# Battery_Protection.net
KiCad netlist of a schematic drawn in Altium Designer
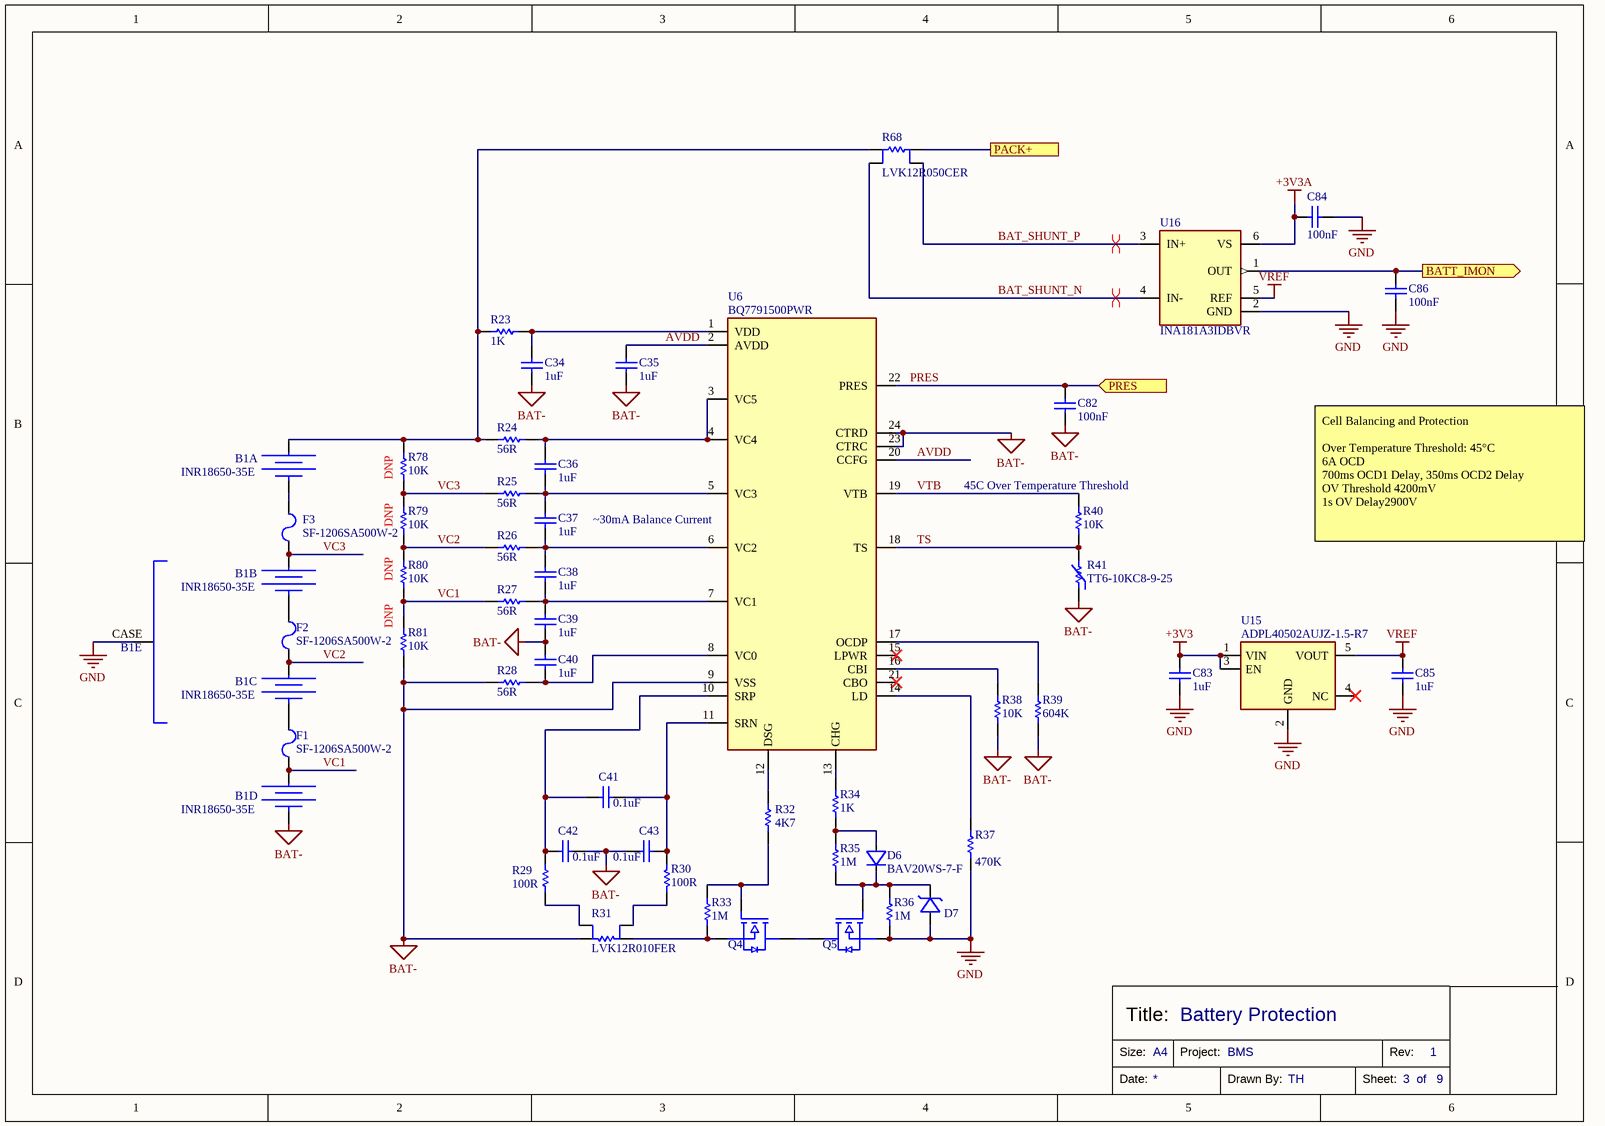
[diagram p0: Battery_Protection.SchDoc]

(export (version "E")
  (design (tool "Eeschema 10.0.6"))
  (components
    (comp (ref "B1")
      (value "INR18650-35E")
      (footprint "4S Battery Direct Solder")
      (description "Custom 4S battery component for Cubesat EPS")
      (libsource (lib "Ahristi_Library") (part "4S Battery Split"))
    )
    (comp (ref "C34")
      (value "CL10A105KB8NNNC")
      (footprint "CAPC0603X040")
      (description "1uF 50V X5R ±10% 0603 Multilayer Ceramic Capacitors MLCC - SMD/SMT ROHS")
      (fields
        (field (name "TOLERANCE") "10%")
        (field (name "DISTRIBUTOR PART NUMBER") "C15849")
        (field (name "CAPACITANCE") "1uF")
      )
      (libsource (lib "Ahristi_Library") (part "CL10A105KB8NNNC"))
    )
    (comp (ref "C35")
      (value "CL10A105KB8NNNC")
      (footprint "CAPC0603X040")
      (description "1uF 50V X5R ±10% 0603 Multilayer Ceramic Capacitors MLCC - SMD/SMT ROHS")
      (fields
        (field (name "TOLERANCE") "10%")
        (field (name "DISTRIBUTOR PART NUMBER") "C15849")
        (field (name "CAPACITANCE") "1uF")
      )
      (libsource (lib "Ahristi_Library") (part "CL10A105KB8NNNC"))
    )
    (comp (ref "C36")
      (value "CL10A105KB8NNNC")
      (footprint "CAPC0603X040")
      (description "1uF 50V X5R ±10% 0603 Multilayer Ceramic Capacitors MLCC - SMD/SMT ROHS")
      (fields
        (field (name "TOLERANCE") "10%")
        (field (name "DISTRIBUTOR PART NUMBER") "C15849")
        (field (name "CAPACITANCE") "1uF")
      )
      (libsource (lib "Ahristi_Library") (part "CL10A105KB8NNNC"))
    )
    (comp (ref "C37")
      (value "CL10A105KB8NNNC")
      (footprint "CAPC0603X040")
      (description "1uF 50V X5R ±10% 0603 Multilayer Ceramic Capacitors MLCC - SMD/SMT ROHS")
      (fields
        (field (name "TOLERANCE") "10%")
        (field (name "DISTRIBUTOR PART NUMBER") "C15849")
        (field (name "CAPACITANCE") "1uF")
      )
      (libsource (lib "Ahristi_Library") (part "CL10A105KB8NNNC"))
    )
    (comp (ref "C38")
      (value "CL10A105KB8NNNC")
      (footprint "CAPC0603X040")
      (description "1uF 50V X5R ±10% 0603 Multilayer Ceramic Capacitors MLCC - SMD/SMT ROHS")
      (fields
        (field (name "TOLERANCE") "10%")
        (field (name "DISTRIBUTOR PART NUMBER") "C15849")
        (field (name "CAPACITANCE") "1uF")
      )
      (libsource (lib "Ahristi_Library") (part "CL10A105KB8NNNC"))
    )
    (comp (ref "C39")
      (value "CL10A105KB8NNNC")
      (footprint "CAPC0603X040")
      (description "1uF 50V X5R ±10% 0603 Multilayer Ceramic Capacitors MLCC - SMD/SMT ROHS")
      (fields
        (field (name "TOLERANCE") "10%")
        (field (name "DISTRIBUTOR PART NUMBER") "C15849")
        (field (name "CAPACITANCE") "1uF")
      )
      (libsource (lib "Ahristi_Library") (part "CL10A105KB8NNNC"))
    )
    (comp (ref "C40")
      (value "CL10A105KB8NNNC")
      (footprint "CAPC0603X040")
      (description "1uF 50V X5R ±10% 0603 Multilayer Ceramic Capacitors MLCC - SMD/SMT ROHS")
      (fields
        (field (name "TOLERANCE") "10%")
        (field (name "DISTRIBUTOR PART NUMBER") "C15849")
        (field (name "CAPACITANCE") "1uF")
      )
      (libsource (lib "Ahristi_Library") (part "CL10A105KB8NNNC"))
    )
    (comp (ref "C41")
      (value "CL05B104KB5NNNC")
      (footprint "CAPC0402X020")
      (description "0.1 µF ±10% 50V Ceramic Capacitor X7R 0402 (1005 Metric)")
      (fields
        (field (name "TOLERANCE") "10%")
        (field (name "DISTRIBUTOR PART NUMBER") "1276-CL05B104KB5NNNCCT-ND")
        (field (name "CAPACITANCE") "0.1uF")
      )
      (libsource (lib "Ahristi_Library") (part "CL05B104KB5NNNC"))
    )
    (comp (ref "C42")
      (value "CL05B104KB5NNNC")
      (footprint "CAPC0402X020")
      (description "0.1 µF ±10% 50V Ceramic Capacitor X7R 0402 (1005 Metric)")
      (fields
        (field (name "TOLERANCE") "10%")
        (field (name "DISTRIBUTOR PART NUMBER") "1276-CL05B104KB5NNNCCT-ND")
        (field (name "CAPACITANCE") "0.1uF")
      )
      (libsource (lib "Ahristi_Library") (part "CL05B104KB5NNNC"))
    )
    (comp (ref "C43")
      (value "CL05B104KB5NNNC")
      (footprint "CAPC0402X020")
      (description "0.1 µF ±10% 50V Ceramic Capacitor X7R 0402 (1005 Metric)")
      (fields
        (field (name "TOLERANCE") "10%")
        (field (name "DISTRIBUTOR PART NUMBER") "1276-CL05B104KB5NNNCCT-ND")
        (field (name "CAPACITANCE") "0.1uF")
      )
      (libsource (lib "Ahristi_Library") (part "CL05B104KB5NNNC"))
    )
    (comp (ref "C82")
      (value "C0603C104K5RACTU")
      (footprint "CAPC0603X040")
      (description "0.1 µF ±10% 50V Ceramic Capacitor X7R 0603 (1608 Metric)")
      (fields
        (field (name "TOLERANCE") "10%")
        (field (name "DISTRIBUTOR PART NUMBER") "399-C0603C104K5RACTUCT-ND")
        (field (name "CAPACITANCE") "100nF")
      )
      (libsource (lib "Ahristi_Library") (part "C0603C104K5RACTU"))
    )
    (comp (ref "C83")
      (value "CL10A105KB8NNNC")
      (footprint "CAPC0603X040")
      (description "1uF 50V X5R ±10% 0603 Multilayer Ceramic Capacitors MLCC - SMD/SMT ROHS")
      (fields
        (field (name "TOLERANCE") "10%")
        (field (name "DISTRIBUTOR PART NUMBER") "C15849")
        (field (name "CAPACITANCE") "1uF")
      )
      (libsource (lib "Ahristi_Library") (part "CL10A105KB8NNNC"))
    )
    (comp (ref "C84")
      (value "C0603C104K5RACTU")
      (footprint "CAPC0603X040")
      (description "0.1 µF ±10% 50V Ceramic Capacitor X7R 0603 (1608 Metric)")
      (fields
        (field (name "TOLERANCE") "10%")
        (field (name "DISTRIBUTOR PART NUMBER") "399-C0603C104K5RACTUCT-ND")
        (field (name "CAPACITANCE") "100nF")
      )
      (libsource (lib "Ahristi_Library") (part "C0603C104K5RACTU"))
    )
    (comp (ref "C85")
      (value "CL10A105KB8NNNC")
      (footprint "CAPC0603X040")
      (description "1uF 50V X5R ±10% 0603 Multilayer Ceramic Capacitors MLCC - SMD/SMT ROHS")
      (fields
        (field (name "TOLERANCE") "10%")
        (field (name "DISTRIBUTOR PART NUMBER") "C15849")
        (field (name "CAPACITANCE") "1uF")
      )
      (libsource (lib "Ahristi_Library") (part "CL10A105KB8NNNC"))
    )
    (comp (ref "C86")
      (value "C0603C104K5RACTU")
      (footprint "CAPC0603X040")
      (description "0.1 µF ±10% 50V Ceramic Capacitor X7R 0603 (1608 Metric)")
      (fields
        (field (name "TOLERANCE") "10%")
        (field (name "DISTRIBUTOR PART NUMBER") "399-C0603C104K5RACTUCT-ND")
        (field (name "CAPACITANCE") "100nF")
      )
      (libsource (lib "Ahristi_Library") (part "C0603C104K5RACTU"))
    )
    (comp (ref "D6")
      (value "BAV20WS-7-F")
      (footprint "SOD-323")
      (description "Small Signal Switching Diode 150V 200mW")
      (fields
        (field (name "PART NUMBER") "BAV20WS-7-F")
        (field (name "DISTRIBUTOR PART NUMBER") "BAV20WS-FDICT-ND")
      )
      (libsource (lib "Ahristi_Library") (part "BAV20WS-7-F0"))
    )
    (comp (ref "D7")
      (value "BZT52C12T-7")
      (footprint "SOD-523")
      (description "Zener Diode 12 V 300 mW ±5% Surface Mount SOD-523")
      (fields (field (name "DISTRIBUTOR PART NUMBER") "621-BZT52C12T-7"))
      (libsource (lib "Ahristi_Library") (part "BZT52C12T-7"))
    )
    (comp (ref "F1")
      (value "SF-1206SA500W-2")
      (footprint "SF-1206SA300W-2")
      (description "Fuse Surface Mount 5A Slow Blow 50A Interrupt 1206")
      (fields
        (field (name "DISTRIBUTOR PART NUMBER") "118-SF-1206SA500W-2CT-ND")
        (field (name "PART NUMBER") "SF-1206SA500W-2")
      )
      (libsource (lib "Ahristi_Library") (part "SF-1206SA300W-2"))
    )
    (comp (ref "F2")
      (value "SF-1206SA500W-2")
      (footprint "SF-1206SA300W-2")
      (description "Fuse Surface Mount 5A Slow Blow 50A Interrupt 1206")
      (fields
        (field (name "DISTRIBUTOR PART NUMBER") "118-SF-1206SA500W-2CT-ND")
        (field (name "PART NUMBER") "SF-1206SA500W-2")
      )
      (libsource (lib "Ahristi_Library") (part "SF-1206SA300W-2"))
    )
    (comp (ref "F3")
      (value "SF-1206SA500W-2")
      (footprint "SF-1206SA300W-2")
      (description "Fuse Surface Mount 5A Slow Blow 50A Interrupt 1206")
      (fields
        (field (name "DISTRIBUTOR PART NUMBER") "118-SF-1206SA500W-2CT-ND")
        (field (name "PART NUMBER") "SF-1206SA500W-2")
      )
      (libsource (lib "Ahristi_Library") (part "SF-1206SA300W-2"))
    )
    (comp (ref "Q4")
      (value "BSC026N08NS5")
      (footprint "PG-TDSON-8-5")
      (description "80V N-Channel 23A (Ta), 100A (Tc) 2.5W (Ta), 156W (Tc) Surface Mount PG-TDSON-8-6")
      (fields (field (name "DISTRIBUTOR PART NUMBER") "726-BSC026N08NS5ATMA"))
      (libsource (lib "Ahristi_Library") (part "BSC026N08NS5"))
    )
    (comp (ref "Q5")
      (value "BSC026N08NS5")
      (footprint "PG-TDSON-8-5")
      (description "80V N-Channel 23A (Ta), 100A (Tc) 2.5W (Ta), 156W (Tc) Surface Mount PG-TDSON-8-6")
      (fields (field (name "DISTRIBUTOR PART NUMBER") "726-BSC026N08NS5ATMA"))
      (libsource (lib "Ahristi_Library") (part "BSC026N08NS5"))
    )
    (comp (ref "R23")
      (value "RMCF0603FT1K00")
      (footprint "RESC0603")
      (description "1 kOhms ±1% 0.1W, 1/10W Chip Resistor 0603 (1608 Metric) Automotive AEC-Q200 Thick Film")
      (fields
        (field (name "TOLERANCE") "1%")
        (field (name "DISTRIBUTOR PART NUMBER") "RMCF0603FT1K00CT-ND")
        (field (name "RESISTANCE") "1K")
      )
      (libsource (lib "Ahristi_Library") (part "RMCF0603FT1K00"))
    )
    (comp (ref "R24")
      (value "RMCF0603FT56R0")
      (footprint "RESC0603")
      (description "56 Ohms ±1% 0.1W, 1/10W Chip Resistor 0603 (1608 Metric) Automotive AEC-Q200 Thick Film")
      (fields
        (field (name "TOLERANCE") "1%")
        (field (name "DISTRIBUTOR PART NUMBER") "RMCF0603FT56R0CT-ND")
        (field (name "RESISTANCE") "56R")
      )
      (libsource (lib "Ahristi_Library") (part "RMCF0603FT56R0"))
    )
    (comp (ref "R25")
      (value "RMCF0603FT56R0")
      (footprint "RESC0603")
      (description "56 Ohms ±1% 0.1W, 1/10W Chip Resistor 0603 (1608 Metric) Automotive AEC-Q200 Thick Film")
      (fields
        (field (name "TOLERANCE") "1%")
        (field (name "DISTRIBUTOR PART NUMBER") "RMCF0603FT56R0CT-ND")
        (field (name "RESISTANCE") "56R")
      )
      (libsource (lib "Ahristi_Library") (part "RMCF0603FT56R0"))
    )
    (comp (ref "R26")
      (value "RMCF0603FT56R0")
      (footprint "RESC0603")
      (description "56 Ohms ±1% 0.1W, 1/10W Chip Resistor 0603 (1608 Metric) Automotive AEC-Q200 Thick Film")
      (fields
        (field (name "TOLERANCE") "1%")
        (field (name "DISTRIBUTOR PART NUMBER") "RMCF0603FT56R0CT-ND")
        (field (name "RESISTANCE") "56R")
      )
      (libsource (lib "Ahristi_Library") (part "RMCF0603FT56R0"))
    )
    (comp (ref "R27")
      (value "RMCF0603FT56R0")
      (footprint "RESC0603")
      (description "56 Ohms ±1% 0.1W, 1/10W Chip Resistor 0603 (1608 Metric) Automotive AEC-Q200 Thick Film")
      (fields
        (field (name "TOLERANCE") "1%")
        (field (name "DISTRIBUTOR PART NUMBER") "RMCF0603FT56R0CT-ND")
        (field (name "RESISTANCE") "56R")
      )
      (libsource (lib "Ahristi_Library") (part "RMCF0603FT56R0"))
    )
    (comp (ref "R28")
      (value "RMCF0603FT56R0")
      (footprint "RESC0603")
      (description "56 Ohms ±1% 0.1W, 1/10W Chip Resistor 0603 (1608 Metric) Automotive AEC-Q200 Thick Film")
      (fields
        (field (name "TOLERANCE") "1%")
        (field (name "DISTRIBUTOR PART NUMBER") "RMCF0603FT56R0CT-ND")
        (field (name "RESISTANCE") "56R")
      )
      (libsource (lib "Ahristi_Library") (part "RMCF0603FT56R0"))
    )
    (comp (ref "R29")
      (value "RMCF0603FT100R")
      (footprint "RESC0603")
      (description "100 Ohms ±1% 0.1W, 1/10W Chip Resistor 0603 (1608 Metric) Automotive AEC-Q200 Thick Film")
      (fields
        (field (name "TOLERANCE") "1%")
        (field (name "DISTRIBUTOR PART NUMBER") "RMCF0603FT100RCT-ND")
        (field (name "RESISTANCE") "100R")
      )
      (libsource (lib "Ahristi_Library") (part "RMCF0603FT100R"))
    )
    (comp (ref "R30")
      (value "RMCF0603FT100R")
      (footprint "RESC0603")
      (description "100 Ohms ±1% 0.1W, 1/10W Chip Resistor 0603 (1608 Metric) Automotive AEC-Q200 Thick Film")
      (fields
        (field (name "TOLERANCE") "1%")
        (field (name "DISTRIBUTOR PART NUMBER") "RMCF0603FT100RCT-ND")
        (field (name "RESISTANCE") "100R")
      )
      (libsource (lib "Ahristi_Library") (part "RMCF0603FT100R"))
    )
    (comp (ref "R31")
      (value "LVK12R010FER")
      (footprint "LVK12R050CER-2")
      (fields
        (field (name "DISTRIBUTOR PART NUMBER") "273-LVK12R010FERCT-ND")
        (field (name "MANUFACTURER") "Ohmite")
        (field (name "POWER") "0.5W")
      )
      (libsource (lib "Ahristi_Library") (part "LVK12R010FER"))
    )
    (comp (ref "R32")
      (value "RMCF0603FT4K7")
      (footprint "RESC0603")
      (description "4.7 kOhms ±1% 0.1W, 1/10W Chip Resistor 0603 (1608 Metric) Automotive AEC-Q200 Thick Film")
      (fields
        (field (name "TOLERANCE") "1%")
        (field (name "DISTRIBUTOR PART NUMBER") "RMCF0603FT4K70CT-ND")
        (field (name "RESISTANCE") "4K7")
      )
      (libsource (lib "Ahristi_Library") (part "RMCF0603FT4K7"))
    )
    (comp (ref "R33")
      (value "RMCF0603FT1M00")
      (footprint "RESC0603")
      (description "1 MOhms ±1% 0.1W, 1/10W Chip Resistor 0603 (1608 Metric) Automotive AEC-Q200 Thick Film")
      (fields
        (field (name "TOLERANCE") "1%")
        (field (name "DISTRIBUTOR PART NUMBER") "RMCF0603FT1M00CT-ND")
        (field (name "RESISTANCE") "1M")
      )
      (libsource (lib "Ahristi_Library") (part "RMCF0603FT1M00"))
    )
    (comp (ref "R34")
      (value "RMCF0603FT1K00")
      (footprint "RESC0603")
      (description "1 kOhms ±1% 0.1W, 1/10W Chip Resistor 0603 (1608 Metric) Automotive AEC-Q200 Thick Film")
      (fields
        (field (name "TOLERANCE") "1%")
        (field (name "DISTRIBUTOR PART NUMBER") "RMCF0603FT1K00CT-ND")
        (field (name "RESISTANCE") "1K")
      )
      (libsource (lib "Ahristi_Library") (part "RMCF0603FT1K00"))
    )
    (comp (ref "R35")
      (value "RMCF0603FT1M00")
      (footprint "RESC0603")
      (description "1 MOhms ±1% 0.1W, 1/10W Chip Resistor 0603 (1608 Metric) Automotive AEC-Q200 Thick Film")
      (fields
        (field (name "TOLERANCE") "1%")
        (field (name "DISTRIBUTOR PART NUMBER") "RMCF0603FT1M00CT-ND")
        (field (name "RESISTANCE") "1M")
      )
      (libsource (lib "Ahristi_Library") (part "RMCF0603FT1M00"))
    )
    (comp (ref "R36")
      (value "RMCF0603FT1M00")
      (footprint "RESC0603")
      (description "1 MOhms ±1% 0.1W, 1/10W Chip Resistor 0603 (1608 Metric) Automotive AEC-Q200 Thick Film")
      (fields
        (field (name "TOLERANCE") "1%")
        (field (name "DISTRIBUTOR PART NUMBER") "RMCF0603FT1M00CT-ND")
        (field (name "RESISTANCE") "1M")
      )
      (libsource (lib "Ahristi_Library") (part "RMCF0603FT1M00"))
    )
    (comp (ref "R37")
      (value "RMCF0603FT470K")
      (footprint "RESC0603")
      (description "470 kOhms ±1% 0.1W, 1/10W Chip Resistor 0603 (1608 Metric) Automotive AEC-Q200 Thick Film")
      (fields
        (field (name "TOLERANCE") "1%")
        (field (name "DISTRIBUTOR PART NUMBER") "RMCF0603FT470KCT-ND")
        (field (name "RESISTANCE") "470K")
      )
      (libsource (lib "Ahristi_Library") (part "RMCF0603FT470K"))
    )
    (comp (ref "R38")
      (value "RMCF0603FT10K0")
      (footprint "RESC0603")
      (description "10 kOhms ±1% 0.1W, 1/10W Chip Resistor 0603 (1608 Metric) Automotive AEC-Q200 Thick Film")
      (fields
        (field (name "TOLERANCE") "1%")
        (field (name "DISTRIBUTOR PART NUMBER") "RMCF0603FT10K0CT-ND")
        (field (name "RESISTANCE") "10K")
      )
      (libsource (lib "Ahristi_Library") (part "RMCF0603FT10K0"))
    )
    (comp (ref "R39")
      (value "RMCF0603FT604K")
      (footprint "RESC0603")
      (description "604 kOhms ±1% 0.1W, 1/10W Chip Resistor 0603 (1608 Metric) Automotive AEC-Q200 Thick Film")
      (fields
        (field (name "TOLERANCE") "1%")
        (field (name "DISTRIBUTOR PART NUMBER") "RMCF0603FT604KCT-ND")
        (field (name "RESISTANCE") "604K")
      )
      (libsource (lib "Ahristi_Library") (part "RMCF0603FT604K"))
    )
    (comp (ref "R40")
      (value "RMCF0603FT10K0")
      (footprint "RESC0603")
      (description "10 kOhms ±1% 0.1W, 1/10W Chip Resistor 0603 (1608 Metric) Automotive AEC-Q200 Thick Film")
      (fields
        (field (name "TOLERANCE") "1%")
        (field (name "DISTRIBUTOR PART NUMBER") "RMCF0603FT10K0CT-ND")
        (field (name "RESISTANCE") "10K")
      )
      (libsource (lib "Ahristi_Library") (part "RMCF0603FT10K0"))
    )
    (comp (ref "R41")
      (value "TT6-10KC8-9-25")
      (footprint "TT6-10KC8-9-25")
      (description "NTC Thermistor 10k Probe")
      (fields (field (name "DISTRIBUTOR PART NUMBER") "1912-TT6-10KC8-9-25-ND"))
      (libsource (lib "Ahristi_Library") (part "TT6-10KC8-9-25"))
    )
    (comp (ref "R68")
      (value "LVK12R050CER")
      (footprint "LVK12R050CER-2")
      (description "Resistor, Current Sense 50 mOhms ±0.25% 0.5W, Moisture Resistant Thick Film")
      (fields
        (field (name "DISTRIBUTOR PART NUMBER") "588-LVK12R050CER")
        (field (name "MANUFACTURER") "Ohmite")
      )
      (libsource (lib "Ahristi_Library") (part "LVK12R050CER"))
    )
    (comp (ref "R78")
      (value "RMCF0603FT10K0")
      (footprint "RESC0603")
      (description "10 kOhms ±1% 0.1W, 1/10W Chip Resistor 0603 (1608 Metric) Automotive AEC-Q200 Thick Film")
      (fields
        (field (name "TOLERANCE") "1%")
        (field (name "DISTRIBUTOR PART NUMBER") "RMCF0603FT10K0CT-ND")
        (field (name "RESISTANCE") "10K")
      )
      (libsource (lib "Ahristi_Library") (part "RMCF0603FT10K0"))
    )
    (comp (ref "R79")
      (value "RMCF0603FT10K0")
      (footprint "RESC0603")
      (description "10 kOhms ±1% 0.1W, 1/10W Chip Resistor 0603 (1608 Metric) Automotive AEC-Q200 Thick Film")
      (fields
        (field (name "TOLERANCE") "1%")
        (field (name "DISTRIBUTOR PART NUMBER") "RMCF0603FT10K0CT-ND")
        (field (name "RESISTANCE") "10K")
      )
      (libsource (lib "Ahristi_Library") (part "RMCF0603FT10K0"))
    )
    (comp (ref "R80")
      (value "RMCF0603FT10K0")
      (footprint "RESC0603")
      (description "10 kOhms ±1% 0.1W, 1/10W Chip Resistor 0603 (1608 Metric) Automotive AEC-Q200 Thick Film")
      (fields
        (field (name "TOLERANCE") "1%")
        (field (name "DISTRIBUTOR PART NUMBER") "RMCF0603FT10K0CT-ND")
        (field (name "RESISTANCE") "10K")
      )
      (libsource (lib "Ahristi_Library") (part "RMCF0603FT10K0"))
    )
    (comp (ref "R81")
      (value "RMCF0603FT10K0")
      (footprint "RESC0603")
      (description "10 kOhms ±1% 0.1W, 1/10W Chip Resistor 0603 (1608 Metric) Automotive AEC-Q200 Thick Film")
      (fields
        (field (name "TOLERANCE") "1%")
        (field (name "DISTRIBUTOR PART NUMBER") "RMCF0603FT10K0CT-ND")
        (field (name "RESISTANCE") "10K")
      )
      (libsource (lib "Ahristi_Library") (part "RMCF0603FT10K0"))
    )
    (comp (ref "U6")
      (value "BQ7791500PWR")
      (footprint "TSSOP-24")
      (description "Battery Battery Protection IC Lithium Ion/Polymer 24-TSSOP")
      (fields (field (name "DISTRIBUTOR PART NUMBER") "296-50995-1-ND"))
      (libsource (lib "Ahristi_Library") (part "BQ7791500PWR"))
    )
    (comp (ref "U15")
      (value "ADPL40502AUJZ-1.5-R7")
      (footprint "SOT23-5 IC")
      (description "Linear Voltage Regulator IC Positive Fixed 1.5V Output 200mA TSOT-23-5")
      (fields (field (name "DISTRIBUTOR PART NUMBER") "505-ADPL40502AUJZ-1.5-R7CT-ND"))
      (libsource (lib "Ahristi_Library") (part "ADPL40502AUJZ-1.5-R7"))
    )
    (comp (ref "U16")
      (value "INA181A3IDBVR")
      (footprint "SOT23-6 IC")
      (description "Current Sense Amplifier Bidirectional 100V/V")
      (fields (field (name "DISTRIBUTOR PART NUMBER") "296-47658-1-ND"))
      (libsource (lib "Ahristi_Library") (part "INA181A3IDBVR"))
    )
  )
  (nets
    (net (code "1") (name "+3V3") (class "Default")
      (node (ref "C83") (pin "2") (pinfunction "2_2") (pintype "passive"))
      (node (ref "U15") (pin "1") (pinfunction "VIN_1") (pintype "passive"))
      (node (ref "U15") (pin "3") (pinfunction "EN_3") (pintype "passive"))
    )
    (net (code "2") (name "+3V3A") (class "Default")
      (node (ref "C84") (pin "1") (pinfunction "1_1") (pintype "passive"))
      (node (ref "U16") (pin "6") (pinfunction "VS_6") (pintype "passive"))
    )
    (net (code "3") (name "/AVDD") (class "Default")
      (node (ref "C35") (pin "2") (pinfunction "2_2") (pintype "passive"))
      (node (ref "U6") (pin "2") (pinfunction "AVDD_2") (pintype "passive"))
      (node (ref "U6") (pin "20") (pinfunction "CCFG_20") (pintype "passive"))
    )
    (net (code "4") (name "/BATT_IMON") (class "Default")
      (node (ref "C86") (pin "2") (pinfunction "2_2") (pintype "passive"))
      (node (ref "U16") (pin "1") (pinfunction "OUT_1") (pintype "output"))
    )
    (net (code "5") (name "/BAT_SHUNT_N") (class "Default")
      (node (ref "R68") (pin "2") (pinfunction "2_2") (pintype "passive"))
      (node (ref "U16") (pin "4") (pinfunction "IN-_4") (pintype "passive"))
    )
    (net (code "6") (name "/BAT_SHUNT_P") (class "Default")
      (node (ref "R68") (pin "3") (pinfunction "3_3") (pintype "passive"))
      (node (ref "U16") (pin "3") (pinfunction "IN+_3") (pintype "passive"))
    )
    (net (code "7") (name "/PACK+") (class "Default")
      (node (ref "R68") (pin "4") (pinfunction "4_4") (pintype "passive"))
    )
    (net (code "8") (name "/PRES") (class "Default")
      (node (ref "C82") (pin "2") (pinfunction "2_2") (pintype "passive"))
      (node (ref "U6") (pin "22") (pinfunction "PRES_22") (pintype "passive"))
    )
    (net (code "9") (name "/TS") (class "Default")
      (node (ref "R40") (pin "1") (pinfunction "1_1") (pintype "passive"))
      (node (ref "R41") (pin "2") (pinfunction "2_2") (pintype "passive"))
      (node (ref "U6") (pin "18") (pinfunction "TS_18") (pintype "passive"))
    )
    (net (code "10") (name "/VC1") (class "Default")
      (node (ref "B1") (pin "8") (pinfunction "8_8") (pintype "passive"))
      (node (ref "F1") (pin "1") (pinfunction "1_1") (pintype "passive"))
      (node (ref "R27") (pin "1") (pinfunction "1_1") (pintype "passive"))
      (node (ref "R80") (pin "1") (pinfunction "1_1") (pintype "passive"))
      (node (ref "R81") (pin "2") (pinfunction "2_2") (pintype "passive"))
    )
    (net (code "11") (name "/VC2") (class "Default")
      (node (ref "B1") (pin "6") (pinfunction "6_6") (pintype "passive"))
      (node (ref "F2") (pin "1") (pinfunction "1_1") (pintype "passive"))
      (node (ref "R26") (pin "1") (pinfunction "1_1") (pintype "passive"))
      (node (ref "R79") (pin "1") (pinfunction "1_1") (pintype "passive"))
      (node (ref "R80") (pin "2") (pinfunction "2_2") (pintype "passive"))
    )
    (net (code "12") (name "/VC3") (class "Default")
      (node (ref "B1") (pin "4") (pinfunction "4_4") (pintype "passive"))
      (node (ref "F3") (pin "1") (pinfunction "1_1") (pintype "passive"))
      (node (ref "R25") (pin "1") (pinfunction "1_1") (pintype "passive"))
      (node (ref "R78") (pin "1") (pinfunction "1_1") (pintype "passive"))
      (node (ref "R79") (pin "2") (pinfunction "2_2") (pintype "passive"))
    )
    (net (code "13") (name "/VTB") (class "Default")
      (node (ref "R40") (pin "2") (pinfunction "2_2") (pintype "passive"))
      (node (ref "U6") (pin "19") (pinfunction "VTB_19") (pintype "passive"))
    )
    (net (code "14") (name "BAT-") (class "Default")
      (node (ref "B1") (pin "7") (pinfunction "7_7") (pintype "passive"))
      (node (ref "C34") (pin "1") (pinfunction "1_1") (pintype "passive"))
      (node (ref "C35") (pin "1") (pinfunction "1_1") (pintype "passive"))
      (node (ref "C39") (pin "1") (pinfunction "1_1") (pintype "passive"))
      (node (ref "C40") (pin "2") (pinfunction "2_2") (pintype "passive"))
      (node (ref "C42") (pin "2") (pinfunction "2_2") (pintype "passive"))
      (node (ref "C43") (pin "1") (pinfunction "1_1") (pintype "passive"))
      (node (ref "C82") (pin "1") (pinfunction "1_1") (pintype "passive"))
      (node (ref "R28") (pin "1") (pinfunction "1_1") (pintype "passive"))
      (node (ref "R31") (pin "1") (pinfunction "1_1") (pintype "passive"))
      (node (ref "R38") (pin "1") (pinfunction "1_1") (pintype "passive"))
      (node (ref "R39") (pin "1") (pinfunction "1_1") (pintype "passive"))
      (node (ref "R41") (pin "1") (pinfunction "1_1") (pintype "passive"))
      (node (ref "R81") (pin "1") (pinfunction "1_1") (pintype "passive"))
      (node (ref "U6") (pin "23") (pinfunction "CTRC_23") (pintype "passive"))
      (node (ref "U6") (pin "24") (pinfunction "CTRD_24") (pintype "passive"))
      (node (ref "U6") (pin "9") (pinfunction "VSS_9") (pintype "passive"))
    )
    (net (code "15") (name "GND") (class "Default")
      (node (ref "B1") (pin "CASE") (pinfunction "CASE_CASE") (pintype "passive"))
      (node (ref "C83") (pin "1") (pinfunction "1_1") (pintype "passive"))
      (node (ref "C84") (pin "2") (pinfunction "2_2") (pintype "passive"))
      (node (ref "C85") (pin "1") (pinfunction "1_1") (pintype "passive"))
      (node (ref "C86") (pin "1") (pinfunction "1_1") (pintype "passive"))
      (node (ref "D7") (pin "A") (pinfunction "A_A") (pintype "passive"))
      (node (ref "Q5") (pin "S") (pinfunction "S_S") (pintype "passive"))
      (node (ref "R36") (pin "1") (pinfunction "1_1") (pintype "passive"))
      (node (ref "R37") (pin "1") (pinfunction "1_1") (pintype "passive"))
      (node (ref "U15") (pin "2") (pinfunction "GND_2") (pintype "passive"))
      (node (ref "U16") (pin "2") (pinfunction "GND_2") (pintype "passive"))
    )
    (net (code "16") (name "Net-(B1-Pad1)") (class "Default")
      (node (ref "B1") (pin "1") (pinfunction "1_1") (pintype "passive"))
      (node (ref "F3") (pin "2") (pinfunction "2_2") (pintype "passive"))
    )
    (net (code "17") (name "Net-(B1-Pad2)") (class "Default")
      (node (ref "B1") (pin "2") (pinfunction "2_2") (pintype "passive"))
      (node (ref "R23") (pin "1") (pinfunction "1_1") (pintype "passive"))
      (node (ref "R24") (pin "1") (pinfunction "1_1") (pintype "passive"))
      (node (ref "R68") (pin "1") (pinfunction "1_1") (pintype "passive"))
      (node (ref "R78") (pin "2") (pinfunction "2_2") (pintype "passive"))
    )
    (net (code "18") (name "Net-(B1-Pad3)") (class "Default")
      (node (ref "B1") (pin "3") (pinfunction "3_3") (pintype "passive"))
      (node (ref "F2") (pin "2") (pinfunction "2_2") (pintype "passive"))
    )
    (net (code "19") (name "Net-(B1-Pad5)") (class "Default")
      (node (ref "B1") (pin "5") (pinfunction "5_5") (pintype "passive"))
      (node (ref "F1") (pin "2") (pinfunction "2_2") (pintype "passive"))
    )
    (net (code "20") (name "Net-(D6-PadA)") (class "Default")
      (node (ref "D6") (pin "A") (pinfunction "A_A") (pintype "passive"))
      (node (ref "R34") (pin "1") (pinfunction "1_1") (pintype "passive"))
      (node (ref "R35") (pin "2") (pinfunction "2_2") (pintype "passive"))
    )
    (net (code "21") (name "Net-(D6-PadK)") (class "Default")
      (node (ref "D6") (pin "K") (pinfunction "K_K") (pintype "passive"))
      (node (ref "D7") (pin "K") (pinfunction "K_K") (pintype "passive"))
      (node (ref "Q5") (pin "G") (pinfunction "G_G") (pintype "passive"))
      (node (ref "R35") (pin "1") (pinfunction "1_1") (pintype "passive"))
      (node (ref "R36") (pin "2") (pinfunction "2_2") (pintype "passive"))
    )
    (net (code "22") (name "Net-(Q4-PadD)") (class "Default")
      (node (ref "Q4") (pin "D") (pinfunction "D_D") (pintype "passive"))
      (node (ref "Q5") (pin "D") (pinfunction "D_D") (pintype "passive"))
    )
    (net (code "23") (name "Net-(Q4-PadG)") (class "Default")
      (node (ref "Q4") (pin "G") (pinfunction "G_G") (pintype "passive"))
      (node (ref "R32") (pin "1") (pinfunction "1_1") (pintype "passive"))
      (node (ref "R33") (pin "2") (pinfunction "2_2") (pintype "passive"))
    )
    (net (code "24") (name "Net-(Q4-PadS)") (class "Default")
      (node (ref "Q4") (pin "S") (pinfunction "S_S") (pintype "passive"))
      (node (ref "R31") (pin "4") (pinfunction "4_4") (pintype "passive"))
      (node (ref "R33") (pin "1") (pinfunction "1_1") (pintype "passive"))
    )
    (net (code "25") (name "Net-(R29-Pad1)") (class "Default")
      (node (ref "R29") (pin "1") (pinfunction "1_1") (pintype "passive"))
      (node (ref "R31") (pin "2") (pinfunction "2_2") (pintype "passive"))
    )
    (net (code "26") (name "Net-(R30-Pad1)") (class "Default")
      (node (ref "R30") (pin "1") (pinfunction "1_1") (pintype "passive"))
      (node (ref "R31") (pin "3") (pinfunction "3_3") (pintype "passive"))
    )
    (net (code "27") (name "Net-(U6-CBI)") (class "Default")
      (node (ref "R38") (pin "2") (pinfunction "2_2") (pintype "passive"))
      (node (ref "U6") (pin "16") (pinfunction "CBI_16") (pintype "passive"))
    )
    (net (code "28") (name "Net-(U6-CHG)") (class "Default")
      (node (ref "R34") (pin "2") (pinfunction "2_2") (pintype "passive"))
      (node (ref "U6") (pin "13") (pinfunction "CHG_13") (pintype "passive"))
    )
    (net (code "29") (name "Net-(U6-DSG)") (class "Default")
      (node (ref "R32") (pin "2") (pinfunction "2_2") (pintype "passive"))
      (node (ref "U6") (pin "12") (pinfunction "DSG_12") (pintype "passive"))
    )
    (net (code "30") (name "Net-(U6-LD)") (class "Default")
      (node (ref "R37") (pin "2") (pinfunction "2_2") (pintype "passive"))
      (node (ref "U6") (pin "14") (pinfunction "LD_14") (pintype "passive"))
    )
    (net (code "31") (name "Net-(U6-OCDP)") (class "Default")
      (node (ref "R39") (pin "2") (pinfunction "2_2") (pintype "passive"))
      (node (ref "U6") (pin "17") (pinfunction "OCDP_17") (pintype "passive"))
    )
    (net (code "32") (name "Net-(U6-SRN)") (class "Default")
      (node (ref "C41") (pin "2") (pinfunction "2_2") (pintype "passive"))
      (node (ref "C43") (pin "2") (pinfunction "2_2") (pintype "passive"))
      (node (ref "R30") (pin "2") (pinfunction "2_2") (pintype "passive"))
      (node (ref "U6") (pin "11") (pinfunction "SRN_11") (pintype "passive"))
    )
    (net (code "33") (name "Net-(U6-SRP)") (class "Default")
      (node (ref "C41") (pin "1") (pinfunction "1_1") (pintype "passive"))
      (node (ref "C42") (pin "1") (pinfunction "1_1") (pintype "passive"))
      (node (ref "R29") (pin "2") (pinfunction "2_2") (pintype "passive"))
      (node (ref "U6") (pin "10") (pinfunction "SRP_10") (pintype "passive"))
    )
    (net (code "34") (name "Net-(U6-VC0)") (class "Default")
      (node (ref "C40") (pin "1") (pinfunction "1_1") (pintype "passive"))
      (node (ref "R28") (pin "2") (pinfunction "2_2") (pintype "passive"))
      (node (ref "U6") (pin "8") (pinfunction "VC0_8") (pintype "passive"))
    )
    (net (code "35") (name "Net-(U6-VC1)") (class "Default")
      (node (ref "C38") (pin "1") (pinfunction "1_1") (pintype "passive"))
      (node (ref "C39") (pin "2") (pinfunction "2_2") (pintype "passive"))
      (node (ref "R27") (pin "2") (pinfunction "2_2") (pintype "passive"))
      (node (ref "U6") (pin "7") (pinfunction "VC1_7") (pintype "passive"))
    )
    (net (code "36") (name "Net-(U6-VC2)") (class "Default")
      (node (ref "C37") (pin "1") (pinfunction "1_1") (pintype "passive"))
      (node (ref "C38") (pin "2") (pinfunction "2_2") (pintype "passive"))
      (node (ref "R26") (pin "2") (pinfunction "2_2") (pintype "passive"))
      (node (ref "U6") (pin "6") (pinfunction "VC2_6") (pintype "passive"))
    )
    (net (code "37") (name "Net-(U6-VC3)") (class "Default")
      (node (ref "C36") (pin "1") (pinfunction "1_1") (pintype "passive"))
      (node (ref "C37") (pin "2") (pinfunction "2_2") (pintype "passive"))
      (node (ref "R25") (pin "2") (pinfunction "2_2") (pintype "passive"))
      (node (ref "U6") (pin "5") (pinfunction "VC3_5") (pintype "passive"))
    )
    (net (code "38") (name "Net-(U6-VC4)") (class "Default")
      (node (ref "C36") (pin "2") (pinfunction "2_2") (pintype "passive"))
      (node (ref "R24") (pin "2") (pinfunction "2_2") (pintype "passive"))
      (node (ref "U6") (pin "3") (pinfunction "VC5_3") (pintype "passive"))
      (node (ref "U6") (pin "4") (pinfunction "VC4_4") (pintype "passive"))
    )
    (net (code "39") (name "Net-(U6-VDD)") (class "Default")
      (node (ref "C34") (pin "2") (pinfunction "2_2") (pintype "passive"))
      (node (ref "R23") (pin "2") (pinfunction "2_2") (pintype "passive"))
      (node (ref "U6") (pin "1") (pinfunction "VDD_1") (pintype "passive"))
    )
    (net (code "40") (name "VREF") (class "Default")
      (node (ref "C85") (pin "2") (pinfunction "2_2") (pintype "passive"))
      (node (ref "U15") (pin "5") (pinfunction "VOUT_5") (pintype "passive"))
      (node (ref "U16") (pin "5") (pinfunction "REF_5") (pintype "passive"))
    )
    (net (code "41") (name "unconnected-(U6-CBO-Pad21)") (class "Default")
      (node (ref "U6") (pin "21") (pinfunction "CBO_21") (pintype "passive+no_connect"))
    )
    (net (code "42") (name "unconnected-(U6-LPWR-Pad15)") (class "Default")
      (node (ref "U6") (pin "15") (pinfunction "LPWR_15") (pintype "passive+no_connect"))
    )
    (net (code "43") (name "unconnected-(U15-NC-Pad4)") (class "Default")
      (node (ref "U15") (pin "4") (pinfunction "NC_4") (pintype "passive+no_connect"))
    )
  )
)
